# Impedance_Measurement_System.net
KiCad netlist of a schematic drawn in EAGLE
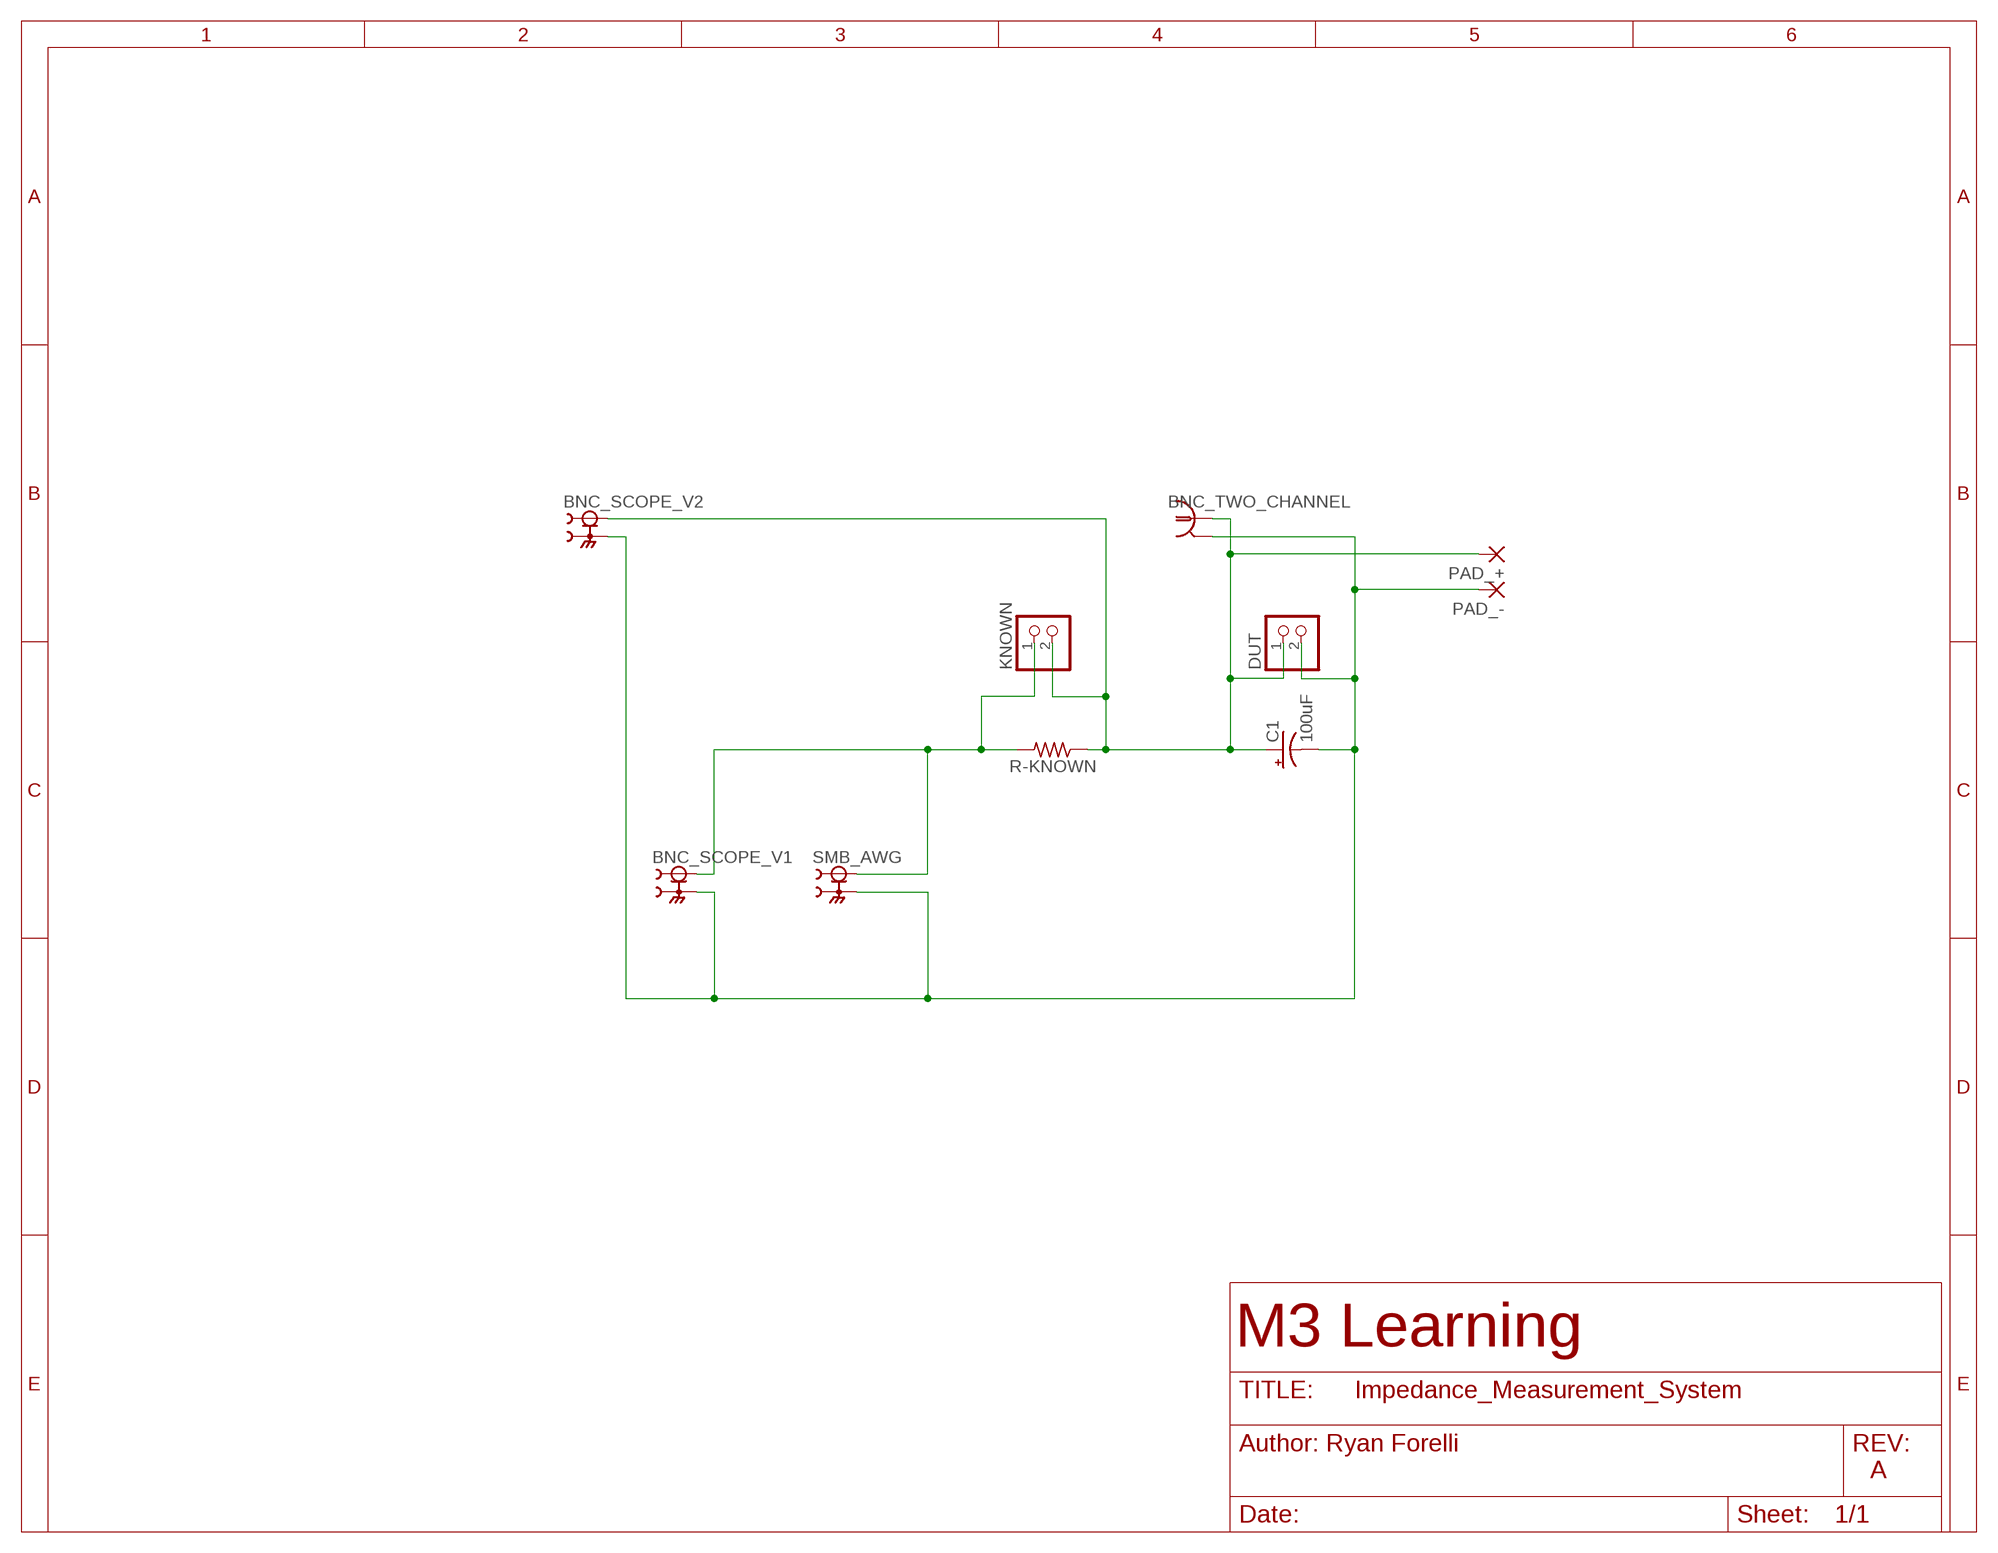
[diagram p0: schematic, sheet 1]

(export (version "E")
  (design (tool "Eeschema 10.0.6"))
  (components
    (comp (ref "BNC_SCOPE_V1")
      (value "CONSMB006-G")
      (footprint "eagle-import:LINX_CONSMB006-G")
      (fields (field (name "MF") "Linx Technologies Inc."))
      (libsource (lib "eagle-import") (part "CONSMB006-G"))
    )
    (comp (ref "BNC_SCOPE_V2")
      (value "CONSMB006-G")
      (footprint "eagle-import:LINX_CONSMB006-G")
      (fields (field (name "MF") "Linx Technologies Inc."))
      (libsource (lib "eagle-import") (part "CONSMB006-G"))
    )
    (comp (ref "BNC_TWO_CHANNEL")
      (value "112404")
      (footprint "eagle-import:112404")
      (fields (field (name "MF") "Amphenol RF"))
      (libsource (lib "eagle-import") (part "112404"))
    )
    (comp (ref "C1")
      (value "100uF")
      (footprint "eagle-import:CPOL-RADIAL-2.5MM-5MM")
      (libsource (lib "eagle-import") (part "10UF-POLAR-RADIAL-2.5MM-25V-20%"))
    )
    (comp (ref "DUT")
      (value "PINHD-1X2")
      (footprint "eagle-import:1X02")
      (libsource (lib "eagle-import") (part "PINHD-1X2"))
    )
    (comp (ref "KNOWN")
      (value "PINHD-1X2")
      (footprint "eagle-import:1X02")
      (libsource (lib "eagle-import") (part "PINHD-1X2"))
    )
    (comp (ref "PAD_+")
      (value "SMD5")
      (footprint "eagle-import:SMD2,54-5,08")
      (libsource (lib "eagle-import") (part "SMD5"))
    )
    (comp (ref "PAD_-")
      (value "SMD5")
      (footprint "eagle-import:SMD2,54-5,08")
      (libsource (lib "eagle-import") (part "SMD5"))
    )
    (comp (ref "R-KNOWN")
      (value "10K")
      (footprint "eagle-import:0204_7")
      (libsource (lib "eagle-import") (part "R-US_0204/7"))
    )
    (comp (ref "SMB_AWG")
      (value "CONSMB006-G")
      (footprint "eagle-import:LINX_CONSMB006-G")
      (fields (field (name "MF") "Linx Technologies Inc."))
      (libsource (lib "eagle-import") (part "CONSMB006-G"))
    )
  )
  (nets
    (net (code "1") (name "Net-(BNC_SCOPE_V1-Pad1)") (class "Default")
      (node (ref "BNC_SCOPE_V1") (pin "1") (pinfunction "1_1") (pintype "passive"))
      (node (ref "KNOWN") (pin "1") (pinfunction "1_1") (pintype "passive"))
      (node (ref "R-KNOWN") (pin "2") (pinfunction "2_2") (pintype "passive"))
      (node (ref "SMB_AWG") (pin "1") (pinfunction "1_1") (pintype "passive"))
    )
    (net (code "2") (name "Net-(C1-+)") (class "Default")
      (node (ref "BNC_SCOPE_V2") (pin "1") (pinfunction "1_1") (pintype "passive"))
      (node (ref "BNC_TWO_CHANNEL") (pin "1") (pinfunction "1_1") (pintype "passive"))
      (node (ref "C1") (pin "1") (pinfunction "+_1") (pintype "passive"))
      (node (ref "DUT") (pin "1") (pinfunction "1_1") (pintype "passive"))
      (node (ref "KNOWN") (pin "2") (pinfunction "2_2") (pintype "passive"))
      (node (ref "PAD_+") (pin "1") (pinfunction "P_1") (pintype "passive"))
      (node (ref "R-KNOWN") (pin "1") (pinfunction "1_1") (pintype "passive"))
    )
    (net (code "3") (name "Net-(C1--)") (class "Default")
      (node (ref "BNC_SCOPE_V1") (pin "G1") (pinfunction "2_G1") (pintype "passive"))
      (node (ref "BNC_SCOPE_V1") (pin "G2") (pinfunction "2_G2") (pintype "passive"))
      (node (ref "BNC_SCOPE_V1") (pin "G3") (pinfunction "2_G3") (pintype "passive"))
      (node (ref "BNC_SCOPE_V1") (pin "G4") (pinfunction "2_G4") (pintype "passive"))
      (node (ref "BNC_SCOPE_V2") (pin "G1") (pinfunction "2_G1") (pintype "passive"))
      (node (ref "BNC_SCOPE_V2") (pin "G2") (pinfunction "2_G2") (pintype "passive"))
      (node (ref "BNC_SCOPE_V2") (pin "G3") (pinfunction "2_G3") (pintype "passive"))
      (node (ref "BNC_SCOPE_V2") (pin "G4") (pinfunction "2_G4") (pintype "passive"))
      (node (ref "BNC_TWO_CHANNEL") (pin "2") (pinfunction "2_2") (pintype "passive"))
      (node (ref "BNC_TWO_CHANNEL") (pin "3") (pinfunction "2_3") (pintype "passive"))
      (node (ref "BNC_TWO_CHANNEL") (pin "4") (pinfunction "2_4") (pintype "passive"))
      (node (ref "BNC_TWO_CHANNEL") (pin "5") (pinfunction "2_5") (pintype "passive"))
      (node (ref "C1") (pin "2") (pinfunction "-_2") (pintype "passive"))
      (node (ref "DUT") (pin "2") (pinfunction "2_2") (pintype "passive"))
      (node (ref "PAD_-") (pin "1") (pinfunction "P_1") (pintype "passive"))
      (node (ref "SMB_AWG") (pin "G1") (pinfunction "2_G1") (pintype "passive"))
      (node (ref "SMB_AWG") (pin "G2") (pinfunction "2_G2") (pintype "passive"))
      (node (ref "SMB_AWG") (pin "G3") (pinfunction "2_G3") (pintype "passive"))
      (node (ref "SMB_AWG") (pin "G4") (pinfunction "2_G4") (pintype "passive"))
    )
  )
)
